# sensor_v3.net
KiCad netlist of a schematic drawn in EAGLE
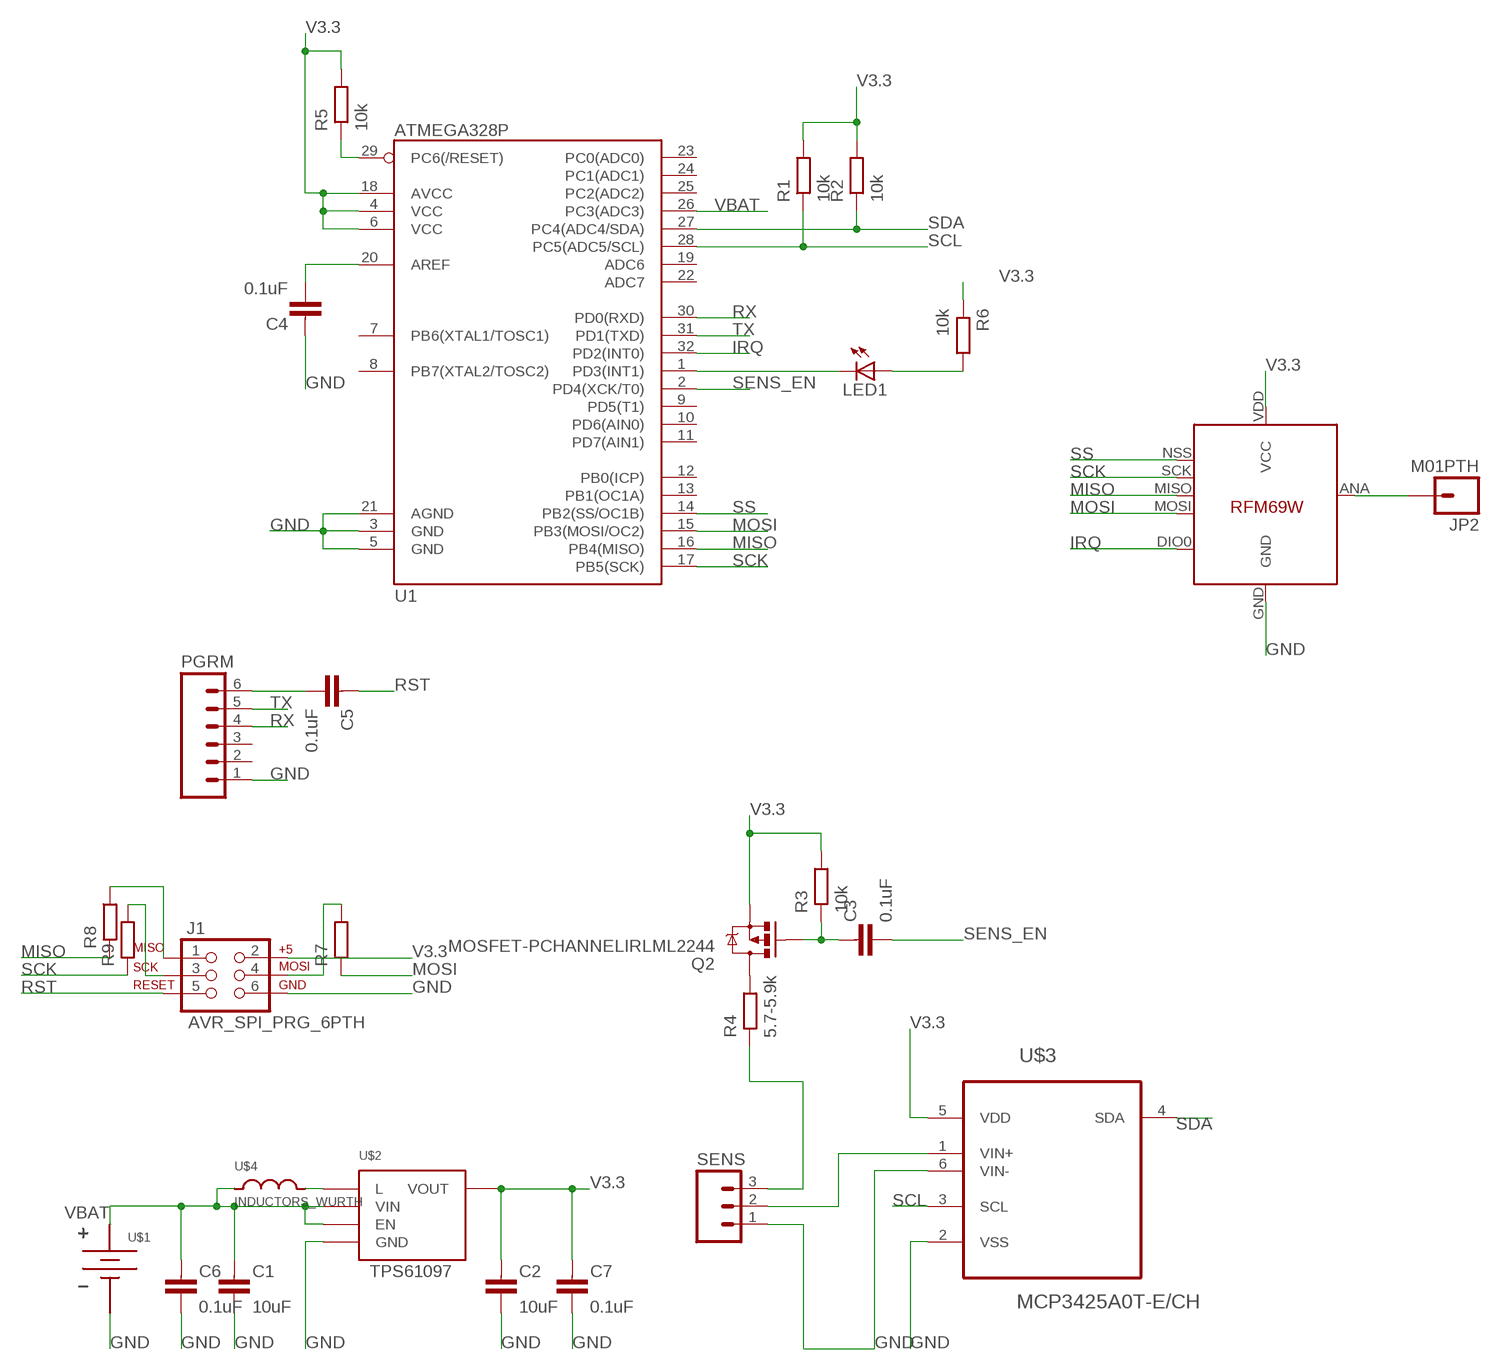
[diagram p0: schematic, sheet 1]

(export (version "E")
  (design (tool "Eeschema 10.0.6"))
  (components
    (comp (ref "C1")
      (value "10uF")
      (footprint "eagle-import:C0805-N")
      (libsource (lib "eagle-import") (part "CAPACITOR0805-N"))
    )
    (comp (ref "C2")
      (value "10uF")
      (footprint "eagle-import:C0805-N")
      (libsource (lib "eagle-import") (part "CAPACITOR0805-N"))
    )
    (comp (ref "C3")
      (value "0.1uF")
      (footprint "eagle-import:C0603-N")
      (libsource (lib "eagle-import") (part "CAPACITOR0603-N"))
    )
    (comp (ref "C4")
      (value "0.1uF")
      (footprint "eagle-import:C0603-N")
      (libsource (lib "eagle-import") (part "CAPACITOR0603-N"))
    )
    (comp (ref "C5")
      (value "0.1uF")
      (footprint "eagle-import:C0603-N")
      (libsource (lib "eagle-import") (part "CAPACITOR0603-N"))
    )
    (comp (ref "C6")
      (value "0.1uF")
      (footprint "eagle-import:C0603-N")
      (libsource (lib "eagle-import") (part "CAPACITOR0603-N"))
    )
    (comp (ref "C7")
      (value "0.1uF")
      (footprint "eagle-import:C0603-N")
      (libsource (lib "eagle-import") (part "CAPACITOR0603-N"))
    )
    (comp (ref "J1")
      (value "AVR_SPI_PRG_6PTH")
      (footprint "eagle-import:2X3")
      (libsource (lib "eagle-import") (part "AVR_SPI_PRG_6PTH"))
    )
    (comp (ref "JP2")
      (value "M01PTH")
      (footprint "eagle-import:1X01")
      (libsource (lib "eagle-import") (part "M01PTH"))
    )
    (comp (ref "LED1")
      (value "LED0603")
      (footprint "eagle-import:LED-0603")
      (libsource (lib "eagle-import") (part "LED0603"))
    )
    (comp (ref "PGRM")
      (value "M06LONGPADS")
      (footprint "eagle-import:1X06_LONGPADS")
      (libsource (lib "eagle-import") (part "M06LONGPADS"))
    )
    (comp (ref "Q2")
      (value "MOSFET-PCHANNELIRLML2244")
      (footprint "eagle-import:SOT23-3")
      (libsource (lib "eagle-import") (part "MOSFET-PCHANNELIRLML2244"))
    )
    (comp (ref "R1")
      (value "10k")
      (footprint "eagle-import:R0603-N")
      (libsource (lib "eagle-import") (part "RESISTOR0603-N"))
    )
    (comp (ref "R2")
      (value "10k")
      (footprint "eagle-import:R0603-N")
      (libsource (lib "eagle-import") (part "RESISTOR0603-N"))
    )
    (comp (ref "R3")
      (value "10k")
      (footprint "eagle-import:R0603-N")
      (libsource (lib "eagle-import") (part "RESISTOR0603-N"))
    )
    (comp (ref "R4")
      (value "5.7-5.9k")
      (footprint "eagle-import:R0603-N")
      (libsource (lib "eagle-import") (part "RESISTOR0603-N"))
    )
    (comp (ref "R5")
      (value "10k")
      (footprint "eagle-import:R0603-N")
      (libsource (lib "eagle-import") (part "RESISTOR0603-N"))
    )
    (comp (ref "R6")
      (value "10k")
      (footprint "eagle-import:R0603-N")
      (libsource (lib "eagle-import") (part "RESISTOR0603-N"))
    )
    (comp (ref "R7")
      (value "RESISTOR1206-N")
      (footprint "eagle-import:R1206-N")
      (libsource (lib "eagle-import") (part "RESISTOR1206-N"))
    )
    (comp (ref "R8")
      (value "RESISTOR1206-N")
      (footprint "eagle-import:R1206-N")
      (libsource (lib "eagle-import") (part "RESISTOR1206-N"))
    )
    (comp (ref "R9")
      (value "RESISTOR1206-N")
      (footprint "eagle-import:R1206-N")
      (libsource (lib "eagle-import") (part "RESISTOR1206-N"))
    )
    (comp (ref "SENS")
      (value "M03PTH")
      (footprint "eagle-import:1X03")
      (libsource (lib "eagle-import") (part "M03PTH"))
    )
    (comp (ref "U$1")
      (value "KEYSTONEAAHOLDER_2CELL")
      (footprint "eagle-import:KEYSTONEAAHOLDER_2CELL")
      (libsource (lib "eagle-import") (part "KEYSTONEAAHOLDER_2CELL"))
    )
    (comp (ref "U$2")
      (value "TPS61097-33")
      (footprint "eagle-import:SOT23-5")
      (libsource (lib "eagle-import") (part "TPS61097-33"))
    )
    (comp (ref "U$3")
      (value "MCP3425A0T-E/CH")
      (footprint "eagle-import:SOT95P270X145-6N")
      (libsource (lib "eagle-import") (part "MCP3425A0T-E/CH"))
    )
    (comp (ref "U$4")
      (value "INDUCTORS_WURTH")
      (footprint "eagle-import:WURTH_10UH_650MA")
      (libsource (lib "eagle-import") (part "INDUCTORS_WURTH"))
    )
    (comp (ref "U$5")
      (value "RFM69")
      (footprint "eagle-import:RFM69W-MINPADS")
      (libsource (lib "eagle-import") (part "RFM69"))
    )
    (comp (ref "U1")
      (value "ATMEGA328P")
      (footprint "eagle-import:TQFP32-08")
      (libsource (lib "eagle-import") (part "ATMEGA328_SMT"))
    )
  )
  (nets
    (net (code "1") (name "/GND") (class "Default")
      (node (ref "C1") (pin "2") (pinfunction "2_2") (pintype "passive"))
      (node (ref "C2") (pin "2") (pinfunction "2_2") (pintype "passive"))
      (node (ref "C4") (pin "1") (pinfunction "1_1") (pintype "passive"))
      (node (ref "C6") (pin "2") (pinfunction "2_2") (pintype "passive"))
      (node (ref "C7") (pin "2") (pinfunction "2_2") (pintype "passive"))
      (node (ref "J1") (pin "6") (pinfunction "6_6") (pintype "passive"))
      (node (ref "PGRM") (pin "1") (pinfunction "1_1") (pintype "passive"))
      (node (ref "SENS") (pin "1") (pinfunction "1_1") (pintype "passive"))
      (node (ref "U$1") (pin "P$2") (pinfunction "GND_P$2") (pintype "bidirectional"))
      (node (ref "U$2") (pin "P$2") (pinfunction "GND_P$2") (pintype "power_in"))
      (node (ref "U$3") (pin "2") (pinfunction "VSS_2") (pintype "passive"))
      (node (ref "U$3") (pin "6") (pinfunction "VIN-_6") (pintype "input"))
      (node (ref "U$5") (pin "GND") (pinfunction "GND_GND") (pintype "power_in"))
      (node (ref "U1") (pin "21") (pinfunction "AGND_21") (pintype "bidirectional"))
      (node (ref "U1") (pin "3") (pinfunction "GND_3") (pintype "bidirectional"))
      (node (ref "U1") (pin "5") (pinfunction "GND_5") (pintype "bidirectional"))
    )
    (net (code "2") (name "/IRQ") (class "Default")
      (node (ref "U$5") (pin "DIO0") (pinfunction "DIO0_DIO0") (pintype "open_collector"))
      (node (ref "U1") (pin "32") (pinfunction "PD2(INT0)_32") (pintype "bidirectional"))
    )
    (net (code "3") (name "/MISO") (class "Default")
      (node (ref "R8") (pin "1") (pinfunction "P$1_1") (pintype "passive"))
      (node (ref "U$5") (pin "MISO") (pinfunction "MISO_MISO") (pintype "input"))
      (node (ref "U1") (pin "16") (pinfunction "PB4(MISO)_16") (pintype "bidirectional"))
    )
    (net (code "4") (name "/MOSI") (class "Default")
      (node (ref "R7") (pin "1") (pinfunction "P$1_1") (pintype "passive"))
      (node (ref "U$5") (pin "MOSI") (pinfunction "MOSI_MOSI") (pintype "output"))
      (node (ref "U1") (pin "15") (pinfunction "PB3(MOSI/OC2)_15") (pintype "bidirectional"))
    )
    (net (code "5") (name "/RST") (class "Default")
      (node (ref "C5") (pin "1") (pinfunction "1_1") (pintype "passive"))
      (node (ref "J1") (pin "5") (pinfunction "5_5") (pintype "passive"))
      (node (ref "R5") (pin "1") (pinfunction "P$1_1") (pintype "passive"))
      (node (ref "U1") (pin "29") (pinfunction "PC6(/RESET)_29") (pintype "bidirectional"))
    )
    (net (code "6") (name "/RX") (class "Default")
      (node (ref "PGRM") (pin "4") (pinfunction "4_4") (pintype "passive"))
      (node (ref "U1") (pin "30") (pinfunction "PD0(RXD)_30") (pintype "bidirectional"))
    )
    (net (code "7") (name "/SCK") (class "Default")
      (node (ref "R9") (pin "1") (pinfunction "P$1_1") (pintype "passive"))
      (node (ref "U$5") (pin "SCK") (pinfunction "SCK_SCK") (pintype "input"))
      (node (ref "U1") (pin "17") (pinfunction "PB5(SCK)_17") (pintype "bidirectional"))
    )
    (net (code "8") (name "/SCL") (class "Default")
      (node (ref "R1") (pin "1") (pinfunction "P$1_1") (pintype "passive"))
      (node (ref "U$3") (pin "3") (pinfunction "SCL_3") (pintype "input"))
      (node (ref "U1") (pin "28") (pinfunction "PC5(ADC5/SCL)_28") (pintype "bidirectional"))
    )
    (net (code "9") (name "/SDA") (class "Default")
      (node (ref "R2") (pin "1") (pinfunction "P$1_1") (pintype "passive"))
      (node (ref "U$3") (pin "4") (pinfunction "SDA_4") (pintype "bidirectional"))
      (node (ref "U1") (pin "27") (pinfunction "PC4(ADC4/SDA)_27") (pintype "bidirectional"))
    )
    (net (code "10") (name "/SENS_EN") (class "Default")
      (node (ref "C3") (pin "2") (pinfunction "2_2") (pintype "passive"))
      (node (ref "U1") (pin "2") (pinfunction "PD4(XCK/T0)_2") (pintype "bidirectional"))
    )
    (net (code "11") (name "/SS") (class "Default")
      (node (ref "U$5") (pin "NSS") (pinfunction "SEL_NSS") (pintype "input"))
      (node (ref "U1") (pin "14") (pinfunction "PB2(SS/OC1B)_14") (pintype "bidirectional"))
    )
    (net (code "12") (name "/TX") (class "Default")
      (node (ref "PGRM") (pin "5") (pinfunction "5_5") (pintype "passive"))
      (node (ref "U1") (pin "31") (pinfunction "PD1(TXD)_31") (pintype "bidirectional"))
    )
    (net (code "13") (name "/V3.3") (class "Default")
      (node (ref "C2") (pin "1") (pinfunction "1_1") (pintype "passive"))
      (node (ref "C7") (pin "1") (pinfunction "1_1") (pintype "passive"))
      (node (ref "J1") (pin "2") (pinfunction "2_2") (pintype "passive"))
      (node (ref "Q2") (pin "2") (pinfunction "S_2") (pintype "passive"))
      (node (ref "R1") (pin "2") (pinfunction "P$2_2") (pintype "passive"))
      (node (ref "R2") (pin "2") (pinfunction "P$2_2") (pintype "passive"))
      (node (ref "R3") (pin "2") (pinfunction "P$2_2") (pintype "passive"))
      (node (ref "R5") (pin "2") (pinfunction "P$2_2") (pintype "passive"))
      (node (ref "R6") (pin "1") (pinfunction "P$1_1") (pintype "passive"))
      (node (ref "U$2") (pin "P$4") (pinfunction "VOUT_P$4") (pintype "power_in"))
      (node (ref "U$3") (pin "5") (pinfunction "VDD_5") (pintype "power_in"))
      (node (ref "U$5") (pin "VDD") (pinfunction "VCC_VDD") (pintype "power_in"))
      (node (ref "U1") (pin "18") (pinfunction "AVCC_18") (pintype "bidirectional"))
      (node (ref "U1") (pin "4") (pinfunction "VCC_4") (pintype "bidirectional"))
      (node (ref "U1") (pin "6") (pinfunction "VCC_6") (pintype "bidirectional"))
    )
    (net (code "14") (name "/VBAT") (class "Default")
      (node (ref "C1") (pin "1") (pinfunction "1_1") (pintype "passive"))
      (node (ref "C6") (pin "1") (pinfunction "1_1") (pintype "passive"))
      (node (ref "U$1") (pin "P$1") (pinfunction "VBAT_P$1") (pintype "bidirectional"))
      (node (ref "U$2") (pin "P$1") (pinfunction "VIN_P$1") (pintype "power_in"))
      (node (ref "U$2") (pin "P$3") (pinfunction "EN_P$3") (pintype "bidirectional"))
      (node (ref "U$4") (pin "P$2") (pinfunction "P$2_P$2") (pintype "passive"))
      (node (ref "U1") (pin "26") (pinfunction "PC3(ADC3)_26") (pintype "bidirectional"))
    )
    (net (code "15") (name "Net-(C5-Pad2)") (class "Default")
      (node (ref "C5") (pin "2") (pinfunction "2_2") (pintype "passive"))
      (node (ref "PGRM") (pin "6") (pinfunction "6_6") (pintype "passive"))
    )
    (net (code "16") (name "Net-(Q2-D)") (class "Default")
      (node (ref "Q2") (pin "3") (pinfunction "D_3") (pintype "passive"))
      (node (ref "R4") (pin "2") (pinfunction "P$2_2") (pintype "passive"))
    )
    (net (code "17") (name "Net-(Q2-G)") (class "Default")
      (node (ref "C3") (pin "1") (pinfunction "1_1") (pintype "passive"))
      (node (ref "Q2") (pin "1") (pinfunction "G_1") (pintype "passive"))
      (node (ref "R3") (pin "1") (pinfunction "P$1_1") (pintype "passive"))
    )
    (net (code "18") (name "Net-(R4-P$1)") (class "Default")
      (node (ref "R4") (pin "1") (pinfunction "P$1_1") (pintype "passive"))
      (node (ref "SENS") (pin "3") (pinfunction "3_3") (pintype "passive"))
    )
    (net (code "19") (name "Net-(R6-P$2)") (class "Default")
      (node (ref "LED1") (pin "A") (pinfunction "A_A") (pintype "passive"))
      (node (ref "R6") (pin "2") (pinfunction "P$2_2") (pintype "passive"))
    )
    (net (code "20") (name "Net-(R7-P$2)") (class "Default")
      (node (ref "J1") (pin "4") (pinfunction "4_4") (pintype "passive"))
      (node (ref "R7") (pin "2") (pinfunction "P$2_2") (pintype "passive"))
    )
    (net (code "21") (name "Net-(R8-P$2)") (class "Default")
      (node (ref "J1") (pin "1") (pinfunction "1_1") (pintype "passive"))
      (node (ref "R8") (pin "2") (pinfunction "P$2_2") (pintype "passive"))
    )
    (net (code "22") (name "Net-(R9-P$2)") (class "Default")
      (node (ref "J1") (pin "3") (pinfunction "3_3") (pintype "passive"))
      (node (ref "R9") (pin "2") (pinfunction "P$2_2") (pintype "passive"))
    )
    (net (code "23") (name "Net-(U$2-L)") (class "Default")
      (node (ref "U$2") (pin "P$5") (pinfunction "L_P$5") (pintype "bidirectional"))
      (node (ref "U$4") (pin "P$1") (pinfunction "P$1_P$1") (pintype "passive"))
    )
    (net (code "24") (name "Net-(U$3-VIN+)") (class "Default")
      (node (ref "SENS") (pin "2") (pinfunction "2_2") (pintype "passive"))
      (node (ref "U$3") (pin "1") (pinfunction "VIN+_1") (pintype "input"))
    )
    (net (code "25") (name "Net-(U$5-ANT)") (class "Default")
      (node (ref "JP2") (pin "1") (pinfunction "1_1") (pintype "passive"))
      (node (ref "U$5") (pin "ANA") (pinfunction "ANT_ANA") (pintype "passive"))
    )
    (net (code "26") (name "Net-(U1-AREF)") (class "Default")
      (node (ref "C4") (pin "2") (pinfunction "2_2") (pintype "passive"))
      (node (ref "U1") (pin "20") (pinfunction "AREF_20") (pintype "bidirectional"))
    )
    (net (code "27") (name "Net-(U1-PD3(INT1))") (class "Default")
      (node (ref "LED1") (pin "C") (pinfunction "C_C") (pintype "passive"))
      (node (ref "U1") (pin "1") (pinfunction "PD3(INT1)_1") (pintype "bidirectional"))
    )
    (net (code "28") (name "unconnected-(PGRM-Pad2)") (class "Default")
      (node (ref "PGRM") (pin "2") (pinfunction "2_2") (pintype "passive"))
    )
    (net (code "29") (name "unconnected-(PGRM-Pad3)") (class "Default")
      (node (ref "PGRM") (pin "3") (pinfunction "3_3") (pintype "passive"))
    )
    (net (code "30") (name "unconnected-(U1-ADC6-Pad19)") (class "Default")
      (node (ref "U1") (pin "19") (pinfunction "ADC6_19") (pintype "bidirectional"))
    )
    (net (code "31") (name "unconnected-(U1-ADC7-Pad22)") (class "Default")
      (node (ref "U1") (pin "22") (pinfunction "ADC7_22") (pintype "bidirectional"))
    )
    (net (code "32") (name "unconnected-(U1-PB0(ICP)-Pad12)") (class "Default")
      (node (ref "U1") (pin "12") (pinfunction "PB0(ICP)_12") (pintype "bidirectional"))
    )
    (net (code "33") (name "unconnected-(U1-PB1(OC1A)-Pad13)") (class "Default")
      (node (ref "U1") (pin "13") (pinfunction "PB1(OC1A)_13") (pintype "bidirectional"))
    )
    (net (code "34") (name "unconnected-(U1-PB6(XTAL1{slash}TOSC1)-Pad7)") (class "Default")
      (node (ref "U1") (pin "7") (pinfunction "PB6(XTAL1/TOSC1)_7") (pintype "bidirectional"))
    )
    (net (code "35") (name "unconnected-(U1-PB7(XTAL2{slash}TOSC2)-Pad8)") (class "Default")
      (node (ref "U1") (pin "8") (pinfunction "PB7(XTAL2/TOSC2)_8") (pintype "bidirectional"))
    )
    (net (code "36") (name "unconnected-(U1-PC0(ADC0)-Pad23)") (class "Default")
      (node (ref "U1") (pin "23") (pinfunction "PC0(ADC0)_23") (pintype "bidirectional"))
    )
    (net (code "37") (name "unconnected-(U1-PC1(ADC1)-Pad24)") (class "Default")
      (node (ref "U1") (pin "24") (pinfunction "PC1(ADC1)_24") (pintype "bidirectional"))
    )
    (net (code "38") (name "unconnected-(U1-PC2(ADC2)-Pad25)") (class "Default")
      (node (ref "U1") (pin "25") (pinfunction "PC2(ADC2)_25") (pintype "bidirectional"))
    )
    (net (code "39") (name "unconnected-(U1-PD5(T1)-Pad9)") (class "Default")
      (node (ref "U1") (pin "9") (pinfunction "PD5(T1)_9") (pintype "bidirectional"))
    )
    (net (code "40") (name "unconnected-(U1-PD6(AIN0)-Pad10)") (class "Default")
      (node (ref "U1") (pin "10") (pinfunction "PD6(AIN0)_10") (pintype "bidirectional"))
    )
    (net (code "41") (name "unconnected-(U1-PD7(AIN1)-Pad11)") (class "Default")
      (node (ref "U1") (pin "11") (pinfunction "PD7(AIN1)_11") (pintype "bidirectional"))
    )
  )
)
